# USB_DBG.net
KiCad netlist of a schematic drawn in Altium Designer
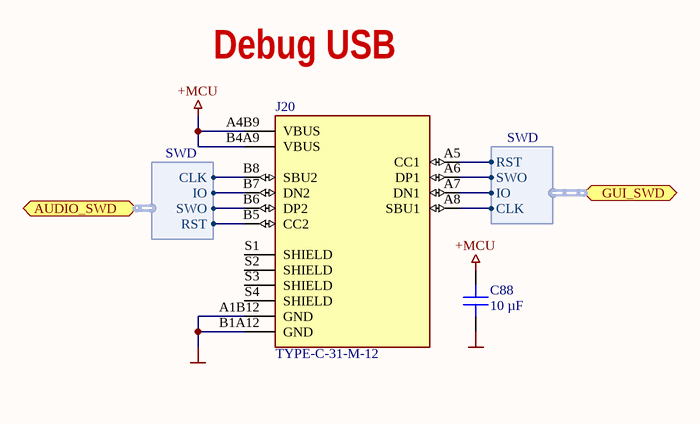
[diagram p0: USB_DBG.SchDoc]

(export (version "E")
  (design (tool "Eeschema 10.0.6"))
  (components
    (comp (ref "C88")
      (value "10 µF")
      (footprint "CAP 0805_2012")
      (description "CAP CER 10UF 10V X5R 0805")
      (fields (field (name "PART NUMBER") "C0805C106K8PAC7800") (field (name "MANUFACTURER") "KEMET"))
      (libsource (lib "Celestial Altium Library - altium_library") (part "Capacitor"))
    )
    (comp (ref "J20")
      (value "TYPE-C-31-M-12")
      (footprint "ProtoStack_H750VBT:HRO_TYPE-C-31-M-12 - REZONIT")
      (description "USB Connectors 24 Receptacle 1 8.94*7.3mm RoHS")
      (fields (field (name "MF") "{'manufacturer': u'HRO Electronics Co., Ltd.'}"))
      (libsource (lib "ProtoStack_H750VBT") (part "TYPE-C-31-M-12"))
    )
  )
  (nets
    (net (code "2") (name "+MCU") (class "Default")
      (node (ref "C88") (pin "2") (pinfunction "2_2") (pintype "passive"))
      (node (ref "J20") (pin "A4B9") (pinfunction "VBUS_A4B9") (pintype "power_in"))
      (node (ref "J20") (pin "B4A9") (pinfunction "VBUS_B4A9") (pintype "power_in"))
    )
    (net (code "4") (name "GND") (class "Default")
      (node (ref "C88") (pin "1") (pinfunction "1_1") (pintype "passive"))
      (node (ref "J20") (pin "A1B12") (pinfunction "GND_A1B12") (pintype "power_in"))
      (node (ref "J20") (pin "B1A12") (pinfunction "GND_B1A12") (pintype "power_in"))
    )
    (net (code "5") (name "unconnected-(J20-CC1-PadA5)") (class "Default")
      (node (ref "J20") (pin "A5") (pinfunction "CC1_A5") (pintype "bidirectional"))
    )
    (net (code "6") (name "unconnected-(J20-CC2-PadB5)") (class "Default")
      (node (ref "J20") (pin "B5") (pinfunction "CC2_B5") (pintype "bidirectional"))
    )
    (net (code "7") (name "unconnected-(J20-DN1-PadA7)") (class "Default")
      (node (ref "J20") (pin "A7") (pinfunction "DN1_A7") (pintype "bidirectional"))
    )
    (net (code "8") (name "unconnected-(J20-DN2-PadB7)") (class "Default")
      (node (ref "J20") (pin "B7") (pinfunction "DN2_B7") (pintype "bidirectional"))
    )
    (net (code "9") (name "unconnected-(J20-DP1-PadA6)") (class "Default")
      (node (ref "J20") (pin "A6") (pinfunction "DP1_A6") (pintype "bidirectional"))
    )
    (net (code "10") (name "unconnected-(J20-DP2-PadB6)") (class "Default")
      (node (ref "J20") (pin "B6") (pinfunction "DP2_B6") (pintype "bidirectional"))
    )
    (net (code "11") (name "unconnected-(J20-SBU1-PadA8)") (class "Default")
      (node (ref "J20") (pin "A8") (pinfunction "SBU1_A8") (pintype "bidirectional"))
    )
    (net (code "12") (name "unconnected-(J20-SBU2-PadB8)") (class "Default")
      (node (ref "J20") (pin "B8") (pinfunction "SBU2_B8") (pintype "bidirectional"))
    )
    (net (code "13") (name "unconnected-(J20-SHIELD-PadS1)") (class "Default")
      (node (ref "J20") (pin "S1") (pinfunction "SHIELD_S1") (pintype "passive"))
    )
    (net (code "14") (name "unconnected-(J20-SHIELD-PadS2)") (class "Default")
      (node (ref "J20") (pin "S2") (pinfunction "SHIELD_S2") (pintype "passive"))
    )
    (net (code "15") (name "unconnected-(J20-SHIELD-PadS3)") (class "Default")
      (node (ref "J20") (pin "S3") (pinfunction "SHIELD_S3") (pintype "passive"))
    )
    (net (code "16") (name "unconnected-(J20-SHIELD-PadS4)") (class "Default")
      (node (ref "J20") (pin "S4") (pinfunction "SHIELD_S4") (pintype "passive"))
    )
  )
)
